# Actuators.net
KiCad netlist of a schematic drawn in Altium Designer
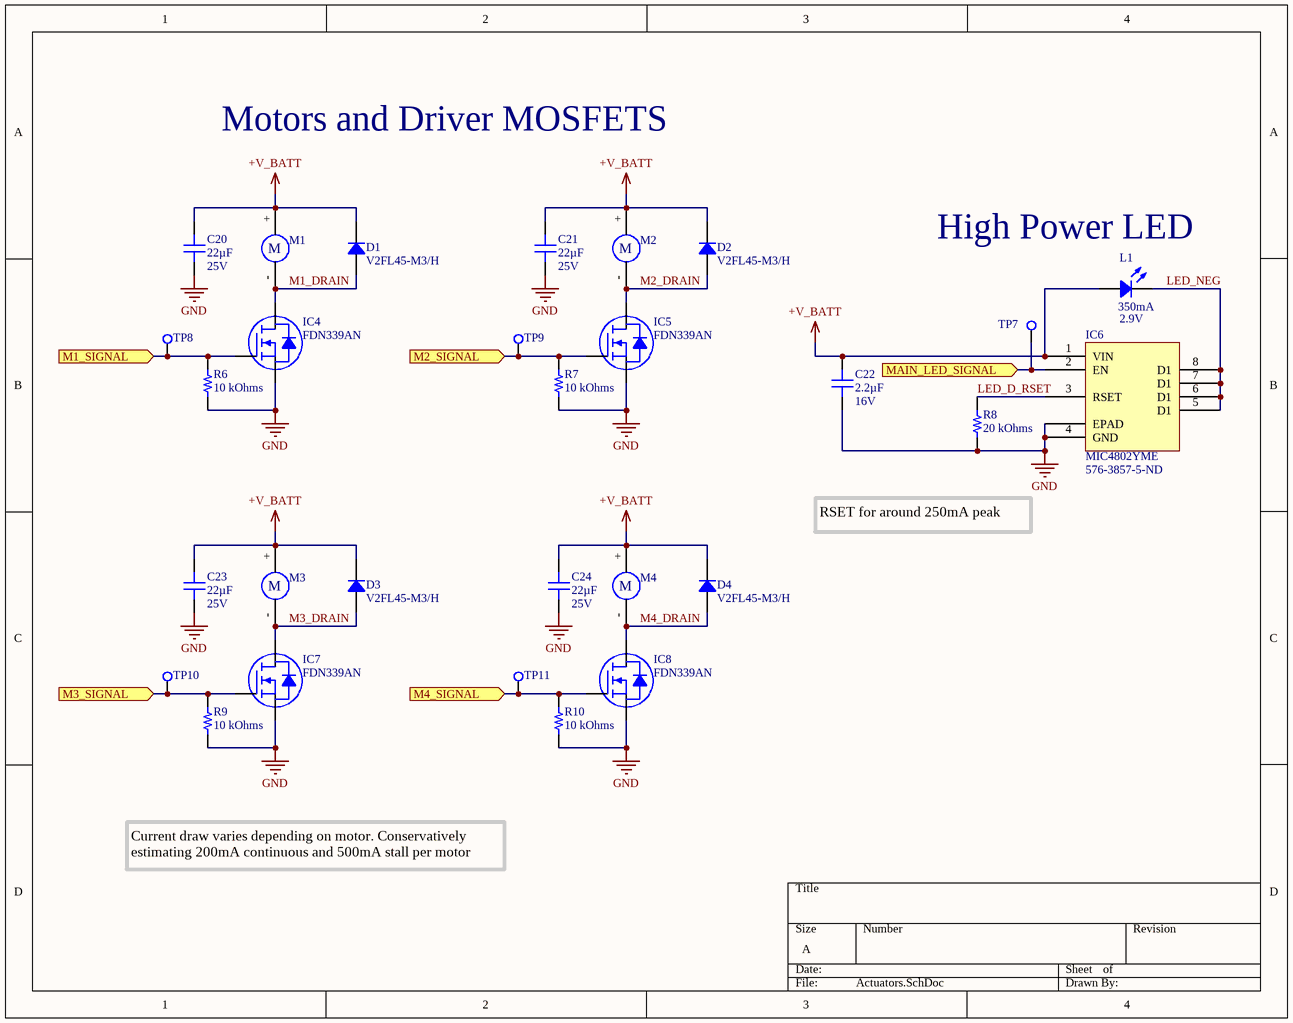
[diagram p0: Actuators.SchDoc]

(export (version "E")
  (design (tool "Eeschema 10.0.6"))
  (components
    (comp (ref "C20")
      (value "22µF")
      (footprint "CAP 1206_3216 - 1.8MM")
      (description "CAP CER 22UF 25V X5R 1206")
      (fields
        (field (name "PART NUMBER") "C3216X5R1E226M160AB")
        (field (name "MANUFACTURER") "TDK Corporation")
        (field (name "VOLTAGE - RATED") "25V")
      )
      (libsource (lib "Celestial Altium Library - altium_library") (part "Capacitor"))
    )
    (comp (ref "C21")
      (value "22µF")
      (footprint "CAP 1206_3216 - 1.8MM")
      (description "CAP CER 22UF 25V X5R 1206")
      (fields
        (field (name "PART NUMBER") "C3216X5R1E226M160AB")
        (field (name "MANUFACTURER") "TDK Corporation")
        (field (name "VOLTAGE - RATED") "25V")
      )
      (libsource (lib "Celestial Altium Library - altium_library") (part "Capacitor"))
    )
    (comp (ref "C22")
      (value "2.2µF")
      (footprint "CAP 0603_1608")
      (description "CAP CER 2.2UF 16V X5R 0603")
      (fields
        (field (name "PART NUMBER") "CC0603KRX5R7BB225")
        (field (name "MANUFACTURER") "Yageo")
        (field (name "VOLTAGE - RATED") "16V")
      )
      (libsource (lib "Celestial Altium Library - altium_library") (part "Capacitor"))
    )
    (comp (ref "C23")
      (value "22µF")
      (footprint "CAP 1206_3216 - 1.8MM")
      (description "CAP CER 22UF 25V X5R 1206")
      (fields
        (field (name "PART NUMBER") "C3216X5R1E226M160AB")
        (field (name "MANUFACTURER") "TDK Corporation")
        (field (name "VOLTAGE - RATED") "25V")
      )
      (libsource (lib "Celestial Altium Library - altium_library") (part "Capacitor"))
    )
    (comp (ref "C24")
      (value "22µF")
      (footprint "CAP 1206_3216 - 1.8MM")
      (description "CAP CER 22UF 25V X5R 1206")
      (fields
        (field (name "PART NUMBER") "C3216X5R1E226M160AB")
        (field (name "MANUFACTURER") "TDK Corporation")
        (field (name "VOLTAGE - RATED") "25V")
      )
      (libsource (lib "Celestial Altium Library - altium_library") (part "Capacitor"))
    )
    (comp (ref "D1")
      (value "V2FL45-M3/H")
      (footprint "SMF DO-219AB")
      (description "2A,45V,SMF,TRENCH SKY RECT.")
      (fields (field (name "MANUFACTURER") "Vishay Semiconductor Diodes Division"))
      (libsource (lib "Celestial Altium Library - altium_library") (part "Diode"))
    )
    (comp (ref "D2")
      (value "V2FL45-M3/H")
      (footprint "SMF DO-219AB")
      (description "2A,45V,SMF,TRENCH SKY RECT.")
      (fields (field (name "MANUFACTURER") "Vishay Semiconductor Diodes Division"))
      (libsource (lib "Celestial Altium Library - altium_library") (part "Diode"))
    )
    (comp (ref "D3")
      (value "V2FL45-M3/H")
      (footprint "SMF DO-219AB")
      (description "2A,45V,SMF,TRENCH SKY RECT.")
      (fields (field (name "MANUFACTURER") "Vishay Semiconductor Diodes Division"))
      (libsource (lib "Celestial Altium Library - altium_library") (part "Diode"))
    )
    (comp (ref "D4")
      (value "V2FL45-M3/H")
      (footprint "SMF DO-219AB")
      (description "2A,45V,SMF,TRENCH SKY RECT.")
      (fields (field (name "MANUFACTURER") "Vishay Semiconductor Diodes Division"))
      (libsource (lib "Celestial Altium Library - altium_library") (part "Diode"))
    )
    (comp (ref "IC4")
      (value "FDN339AN")
      (footprint "ON SEMI SOT-23-3")
      (description "MOSFET N-CH 20V 3A SSOT3")
      (fields (field (name "MANUFACTURER") "ON Semiconductor"))
      (libsource (lib "Celestial Altium Library - altium_library") (part "ON SEMI MOSFET N-CH SOT-23-3"))
    )
    (comp (ref "IC5")
      (value "FDN339AN")
      (footprint "ON SEMI SOT-23-3")
      (description "MOSFET N-CH 20V 3A SSOT3")
      (fields (field (name "MANUFACTURER") "ON Semiconductor"))
      (libsource (lib "Celestial Altium Library - altium_library") (part "ON SEMI MOSFET N-CH SOT-23-3"))
    )
    (comp (ref "IC6")
      (value "MIC4802YME")
      (footprint "SOIC127P610X160_HS-9N")
      (description "MICREL SEMICONDUCTOR - MIC4802YME - LED DVR, 800MA, 1CH, 8SOIC")
      (fields
        (field (name "MANUFACTURER") "Microchip")
        (field (name "SUPPLIER PART NUMBER 1") "576-3857-5-ND")
      )
      (libsource (lib "Drone") (part "MIC4802YME"))
    )
    (comp (ref "IC7")
      (value "FDN339AN")
      (footprint "ON SEMI SOT-23-3")
      (description "MOSFET N-CH 20V 3A SSOT3")
      (fields (field (name "MANUFACTURER") "ON Semiconductor"))
      (libsource (lib "Celestial Altium Library - altium_library") (part "ON SEMI MOSFET N-CH SOT-23-3"))
    )
    (comp (ref "IC8")
      (value "FDN339AN")
      (footprint "ON SEMI SOT-23-3")
      (description "MOSFET N-CH 20V 3A SSOT3")
      (fields (field (name "MANUFACTURER") "ON Semiconductor"))
      (libsource (lib "Celestial Altium Library - altium_library") (part "ON SEMI MOSFET N-CH SOT-23-3"))
    )
    (comp (ref "L1")
      (value "SCP9WTF1HEL1WKG34E")
      (footprint "LED")
      (description "LED Lighting LH181B White, Warm 2700K 2.9V 350mA 120° 2-SMD, No Lead")
      (fields
        (field (name "MANUFACTURER") "Samsung")
        (field (name "TEST CURRENT") "350mA")
        (field (name "FORWARD VOLTAGE") "2.9V")
      )
      (libsource (lib "Drone") (part "SCP9WTF1HEL1WKG34E"))
    )
    (comp (ref "M1")
      (value "Motor Header")
      (footprint "Motor Header")
      (libsource (lib "Drone") (part "Motor Header"))
    )
    (comp (ref "M2")
      (value "Motor Header")
      (footprint "Motor Header")
      (libsource (lib "Drone") (part "Motor Header"))
    )
    (comp (ref "M3")
      (value "Motor Header")
      (footprint "Motor Header")
      (libsource (lib "Drone") (part "Motor Header"))
    )
    (comp (ref "M4")
      (value "Motor Header")
      (footprint "Motor Header")
      (libsource (lib "Drone") (part "Motor Header"))
    )
    (comp (ref "R6")
      (value "10 kOhms")
      (footprint "RES 0603_1608")
      (description "RES SMD 10K OHM 1% 1/10W 0603")
      (fields (field (name "PART NUMBER") "AC0603FR-0710KL") (field (name "MANUFACTURER") "Yageo"))
      (libsource (lib "Celestial Altium Library - altium_library") (part "Resistor"))
    )
    (comp (ref "R7")
      (value "10 kOhms")
      (footprint "RES 0603_1608")
      (description "RES SMD 10K OHM 1% 1/10W 0603")
      (fields (field (name "PART NUMBER") "AC0603FR-0710KL") (field (name "MANUFACTURER") "Yageo"))
      (libsource (lib "Celestial Altium Library - altium_library") (part "Resistor"))
    )
    (comp (ref "R8")
      (value "20 kOhms")
      (footprint "RES 0603_1608")
      (description "RES SMD 20K OHM 1% 1/10W 0603")
      (fields (field (name "PART NUMBER") "AC0603FR-0720KL") (field (name "MANUFACTURER") "Yageo"))
      (libsource (lib "Celestial Altium Library - altium_library") (part "Resistor"))
    )
    (comp (ref "R9")
      (value "10 kOhms")
      (footprint "RES 0603_1608")
      (description "RES SMD 10K OHM 1% 1/10W 0603")
      (fields (field (name "PART NUMBER") "AC0603FR-0710KL") (field (name "MANUFACTURER") "Yageo"))
      (libsource (lib "Celestial Altium Library - altium_library") (part "Resistor"))
    )
    (comp (ref "R10")
      (value "10 kOhms")
      (footprint "RES 0603_1608")
      (description "RES SMD 10K OHM 1% 1/10W 0603")
      (fields (field (name "PART NUMBER") "AC0603FR-0710KL") (field (name "MANUFACTURER") "Yageo"))
      (libsource (lib "Celestial Altium Library - altium_library") (part "Resistor"))
    )
    (comp (ref "TP7")
      (value "TestPoint")
      (footprint "TestPoint")
      (libsource (lib "Drone") (part "TestPoint"))
    )
    (comp (ref "TP8")
      (value "TestPoint")
      (footprint "TestPoint")
      (libsource (lib "Drone") (part "TestPoint"))
    )
    (comp (ref "TP9")
      (value "TestPoint")
      (footprint "TestPoint")
      (libsource (lib "Drone") (part "TestPoint"))
    )
    (comp (ref "TP10")
      (value "TestPoint")
      (footprint "TestPoint")
      (libsource (lib "Drone") (part "TestPoint"))
    )
    (comp (ref "TP11")
      (value "TestPoint")
      (footprint "TestPoint")
      (libsource (lib "Drone") (part "TestPoint"))
    )
  )
  (nets
    (net (code "1") (name "+V_BATT") (class "Default")
      (node (ref "C20") (pin "2") (pinfunction "2_2") (pintype "passive"))
      (node (ref "C21") (pin "2") (pinfunction "2_2") (pintype "passive"))
      (node (ref "C22") (pin "2") (pinfunction "2_2") (pintype "passive"))
      (node (ref "C23") (pin "2") (pinfunction "2_2") (pintype "passive"))
      (node (ref "C24") (pin "2") (pinfunction "2_2") (pintype "passive"))
      (node (ref "D1") (pin "2") (pinfunction "2_2") (pintype "passive"))
      (node (ref "D2") (pin "2") (pinfunction "2_2") (pintype "passive"))
      (node (ref "D3") (pin "2") (pinfunction "2_2") (pintype "passive"))
      (node (ref "D4") (pin "2") (pinfunction "2_2") (pintype "passive"))
      (node (ref "IC6") (pin "1") (pinfunction "VIN_1") (pintype "passive"))
      (node (ref "L1") (pin "Anode") (pinfunction "1_Anode") (pintype "passive"))
      (node (ref "M1") (pin "+") (pinfunction "+_+") (pintype "passive"))
      (node (ref "M2") (pin "+") (pinfunction "+_+") (pintype "passive"))
      (node (ref "M3") (pin "+") (pinfunction "+_+") (pintype "passive"))
      (node (ref "M4") (pin "+") (pinfunction "+_+") (pintype "passive"))
    )
    (net (code "2") (name "/LED_D_RSET") (class "Default")
      (node (ref "IC6") (pin "3") (pinfunction "RSET_3") (pintype "passive"))
      (node (ref "R8") (pin "2") (pinfunction "2_2") (pintype "passive"))
    )
    (net (code "3") (name "/LED_NEG") (class "Default")
      (node (ref "IC6") (pin "5") (pinfunction "D1_5") (pintype "passive"))
      (node (ref "IC6") (pin "6") (pinfunction "D1_6") (pintype "passive"))
      (node (ref "IC6") (pin "7") (pinfunction "D1_7") (pintype "passive"))
      (node (ref "IC6") (pin "8") (pinfunction "D1_8") (pintype "passive"))
      (node (ref "L1") (pin "Cathode") (pinfunction "2_Cathode") (pintype "passive"))
    )
    (net (code "4") (name "/M1_DRAIN") (class "Default")
      (node (ref "D1") (pin "1") (pinfunction "1_1") (pintype "passive"))
      (node (ref "IC4") (pin "3") (pinfunction "D_3") (pintype "passive"))
      (node (ref "M1") (pin "-") (pinfunction "-_-") (pintype "passive"))
    )
    (net (code "5") (name "/M1_SIGNAL") (class "Default")
      (node (ref "IC4") (pin "1") (pinfunction "G_1") (pintype "passive"))
      (node (ref "R6") (pin "2") (pinfunction "2_2") (pintype "passive"))
      (node (ref "TP8") (pin "1") (pinfunction "1_1") (pintype "passive"))
    )
    (net (code "6") (name "/M2_DRAIN") (class "Default")
      (node (ref "D2") (pin "1") (pinfunction "1_1") (pintype "passive"))
      (node (ref "IC5") (pin "3") (pinfunction "D_3") (pintype "passive"))
      (node (ref "M2") (pin "-") (pinfunction "-_-") (pintype "passive"))
    )
    (net (code "7") (name "/M2_SIGNAL") (class "Default")
      (node (ref "IC5") (pin "1") (pinfunction "G_1") (pintype "passive"))
      (node (ref "R7") (pin "2") (pinfunction "2_2") (pintype "passive"))
      (node (ref "TP9") (pin "1") (pinfunction "1_1") (pintype "passive"))
    )
    (net (code "8") (name "/M3_DRAIN") (class "Default")
      (node (ref "D3") (pin "1") (pinfunction "1_1") (pintype "passive"))
      (node (ref "IC7") (pin "3") (pinfunction "D_3") (pintype "passive"))
      (node (ref "M3") (pin "-") (pinfunction "-_-") (pintype "passive"))
    )
    (net (code "9") (name "/M3_SIGNAL") (class "Default")
      (node (ref "IC7") (pin "1") (pinfunction "G_1") (pintype "passive"))
      (node (ref "R9") (pin "2") (pinfunction "2_2") (pintype "passive"))
      (node (ref "TP10") (pin "1") (pinfunction "1_1") (pintype "passive"))
    )
    (net (code "10") (name "/M4_DRAIN") (class "Default")
      (node (ref "D4") (pin "1") (pinfunction "1_1") (pintype "passive"))
      (node (ref "IC8") (pin "3") (pinfunction "D_3") (pintype "passive"))
      (node (ref "M4") (pin "-") (pinfunction "-_-") (pintype "passive"))
    )
    (net (code "11") (name "/M4_SIGNAL") (class "Default")
      (node (ref "IC8") (pin "1") (pinfunction "G_1") (pintype "passive"))
      (node (ref "R10") (pin "2") (pinfunction "2_2") (pintype "passive"))
      (node (ref "TP11") (pin "1") (pinfunction "1_1") (pintype "passive"))
    )
    (net (code "12") (name "/MAIN_LED_SIGNAL") (class "Default")
      (node (ref "IC6") (pin "2") (pinfunction "EN_2") (pintype "passive"))
      (node (ref "TP7") (pin "1") (pinfunction "1_1") (pintype "passive"))
    )
    (net (code "13") (name "GND") (class "Default")
      (node (ref "C20") (pin "1") (pinfunction "1_1") (pintype "passive"))
      (node (ref "C21") (pin "1") (pinfunction "1_1") (pintype "passive"))
      (node (ref "C22") (pin "1") (pinfunction "1_1") (pintype "passive"))
      (node (ref "C23") (pin "1") (pinfunction "1_1") (pintype "passive"))
      (node (ref "C24") (pin "1") (pinfunction "1_1") (pintype "passive"))
      (node (ref "IC4") (pin "2") (pinfunction "S_2") (pintype "passive"))
      (node (ref "IC5") (pin "2") (pinfunction "S_2") (pintype "passive"))
      (node (ref "IC6") (pin "4") (pinfunction "GND_4") (pintype "passive"))
      (node (ref "IC6") (pin "EPAD") (pinfunction "EPAD_EPAD") (pintype "passive"))
      (node (ref "IC7") (pin "2") (pinfunction "S_2") (pintype "passive"))
      (node (ref "IC8") (pin "2") (pinfunction "S_2") (pintype "passive"))
      (node (ref "R10") (pin "1") (pinfunction "1_1") (pintype "passive"))
      (node (ref "R6") (pin "1") (pinfunction "1_1") (pintype "passive"))
      (node (ref "R7") (pin "1") (pinfunction "1_1") (pintype "passive"))
      (node (ref "R8") (pin "1") (pinfunction "1_1") (pintype "passive"))
      (node (ref "R9") (pin "1") (pinfunction "1_1") (pintype "passive"))
    )
  )
)
